# boosst_new.net
KiCad netlist of a schematic drawn in EAGLE
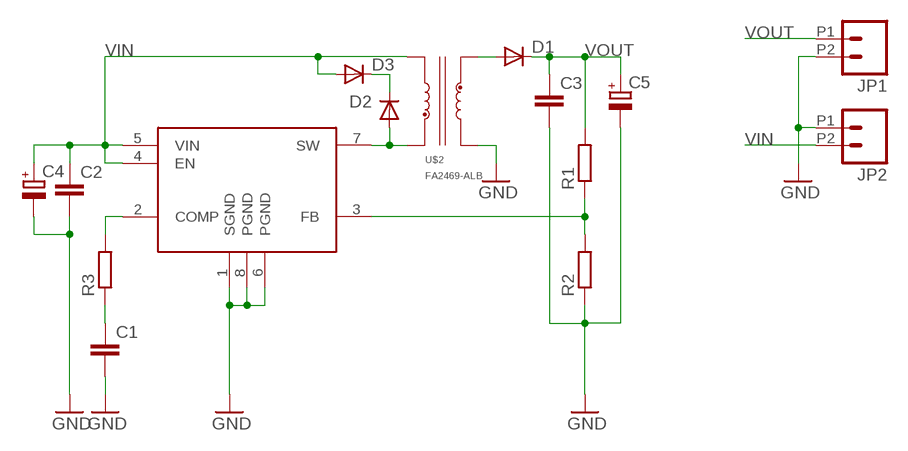
[diagram p0: schematic, sheet 1]

(export (version "E")
  (design (tool "Eeschema 10.0.6"))
  (components
    (comp (ref "C1")
      (value "C-EUC0805")
      (footprint "eagle-import:C0805")
      (libsource (lib "eagle-import") (part "C-EUC0805"))
    )
    (comp (ref "C2")
      (value "C-EUC1210")
      (footprint "eagle-import:C1210")
      (libsource (lib "eagle-import") (part "C-EUC1210"))
    )
    (comp (ref "C3")
      (value "C-EUC1210")
      (footprint "eagle-import:C1210")
      (libsource (lib "eagle-import") (part "C-EUC1210"))
    )
    (comp (ref "C4")
      (value "CPOL-EUE2.5-5")
      (footprint "eagle-import:E2,5-5")
      (libsource (lib "eagle-import") (part "CPOL-EUE2.5-5"))
    )
    (comp (ref "C5")
      (value "CPOL-EUE2.5-5")
      (footprint "eagle-import:E2,5-5")
      (libsource (lib "eagle-import") (part "CPOL-EUE2.5-5"))
    )
    (comp (ref "D1")
      (value "DIODE-DO-214AC")
      (footprint "eagle-import:DO-214AC")
      (libsource (lib "eagle-import") (part "DIODE-DO-214AC"))
    )
    (comp (ref "D2")
      (value "DIODE-SOD-123")
      (footprint "eagle-import:SOD-123")
      (libsource (lib "eagle-import") (part "DIODE-SOD-123"))
    )
    (comp (ref "D3")
      (value "DIODE-SOD-123")
      (footprint "eagle-import:SOD-123")
      (libsource (lib "eagle-import") (part "DIODE-SOD-123"))
    )
    (comp (ref "JP1")
      (value "M022.54MM_SCREWTERM")
      (footprint "eagle-import:1X02_2.54_SCREWTERM")
      (libsource (lib "eagle-import") (part "M022.54MM_SCREWTERM"))
    )
    (comp (ref "JP2")
      (value "M022.54MM_SCREWTERM")
      (footprint "eagle-import:1X02_2.54_SCREWTERM")
      (libsource (lib "eagle-import") (part "M022.54MM_SCREWTERM"))
    )
    (comp (ref "R1")
      (value "R-EU_R0805")
      (footprint "eagle-import:R0805")
      (libsource (lib "eagle-import") (part "R-EU_R0805"))
    )
    (comp (ref "R2")
      (value "R-EU_R0805")
      (footprint "eagle-import:R0805")
      (libsource (lib "eagle-import") (part "R-EU_R0805"))
    )
    (comp (ref "R3")
      (value "R-EU_R0805")
      (footprint "eagle-import:R0805")
      (libsource (lib "eagle-import") (part "R-EU_R0805"))
    )
    (comp (ref "U$1")
      (value "MC3172YM")
      (footprint "eagle-import:SOIC8")
      (libsource (lib "eagle-import") (part "MC3172YM"))
    )
    (comp (ref "U$2")
      (value "FA2469-ALB")
      (footprint "eagle-import:FA2469")
      (libsource (lib "eagle-import") (part "FA2469-ALB"))
    )
  )
  (nets
    (net (code "1") (name "/VIN") (class "Default")
      (node (ref "C2") (pin "1") (pinfunction "1_1") (pintype "passive"))
      (node (ref "C4") (pin "+") (pinfunction "+_+") (pintype "passive"))
      (node (ref "D3") (pin "A") (pinfunction "A_A") (pintype "passive"))
      (node (ref "JP2") (pin "P2") (pinfunction "2_P2") (pintype "passive"))
      (node (ref "U$1") (pin "4") (pinfunction "EN_4") (pintype "bidirectional"))
      (node (ref "U$1") (pin "5") (pinfunction "VIN_5") (pintype "bidirectional"))
      (node (ref "U$2") (pin "3") (pinfunction "3_3") (pintype "passive"))
    )
    (net (code "2") (name "/VOUT") (class "Default")
      (node (ref "C3") (pin "1") (pinfunction "1_1") (pintype "passive"))
      (node (ref "C5") (pin "+") (pinfunction "+_+") (pintype "passive"))
      (node (ref "D1") (pin "1") (pinfunction "C_1") (pintype "passive"))
      (node (ref "JP1") (pin "P1") (pinfunction "1_P1") (pintype "passive"))
      (node (ref "R1") (pin "2") (pinfunction "2_2") (pintype "passive"))
    )
    (net (code "3") (name "GND") (class "Default")
      (node (ref "C1") (pin "2") (pinfunction "2_2") (pintype "passive"))
      (node (ref "C2") (pin "2") (pinfunction "2_2") (pintype "passive"))
      (node (ref "C3") (pin "2") (pinfunction "2_2") (pintype "passive"))
      (node (ref "C4") (pin "-") (pinfunction "-_-") (pintype "passive"))
      (node (ref "C5") (pin "-") (pinfunction "-_-") (pintype "passive"))
      (node (ref "JP1") (pin "P2") (pinfunction "2_P2") (pintype "passive"))
      (node (ref "JP2") (pin "P1") (pinfunction "1_P1") (pintype "passive"))
      (node (ref "R2") (pin "1") (pinfunction "1_1") (pintype "passive"))
      (node (ref "U$1") (pin "1") (pinfunction "SGND_1") (pintype "bidirectional"))
      (node (ref "U$1") (pin "6") (pinfunction "PGND_6") (pintype "bidirectional"))
      (node (ref "U$1") (pin "8") (pinfunction "PGND_8") (pintype "bidirectional"))
      (node (ref "U$2") (pin "6") (pinfunction "6_6") (pintype "passive"))
    )
    (net (code "4") (name "Net-(C1-Pad1)") (class "Default")
      (node (ref "C1") (pin "1") (pinfunction "1_1") (pintype "passive"))
      (node (ref "R3") (pin "1") (pinfunction "1_1") (pintype "passive"))
    )
    (net (code "5") (name "Net-(D1-A)") (class "Default")
      (node (ref "D1") (pin "2") (pinfunction "A_2") (pintype "passive"))
      (node (ref "U$2") (pin "4") (pinfunction "4_4") (pintype "passive"))
    )
    (net (code "6") (name "Net-(D2-PadC)") (class "Default")
      (node (ref "D2") (pin "C") (pinfunction "C_C") (pintype "passive"))
      (node (ref "D3") (pin "C") (pinfunction "C_C") (pintype "passive"))
    )
    (net (code "7") (name "Net-(U$1-COMP)") (class "Default")
      (node (ref "R3") (pin "2") (pinfunction "2_2") (pintype "passive"))
      (node (ref "U$1") (pin "2") (pinfunction "COMP_2") (pintype "bidirectional"))
    )
    (net (code "8") (name "Net-(U$1-FB)") (class "Default")
      (node (ref "R1") (pin "1") (pinfunction "1_1") (pintype "passive"))
      (node (ref "R2") (pin "2") (pinfunction "2_2") (pintype "passive"))
      (node (ref "U$1") (pin "3") (pinfunction "FB_3") (pintype "bidirectional"))
    )
    (net (code "9") (name "Net-(U$1-SW)") (class "Default")
      (node (ref "D2") (pin "A") (pinfunction "A_A") (pintype "passive"))
      (node (ref "U$1") (pin "7") (pinfunction "SW_7") (pintype "bidirectional"))
      (node (ref "U$2") (pin "1") (pinfunction "1_1") (pintype "passive"))
    )
  )
)
